# lab1.net
KiCad netlist of a schematic drawn in Altium Designer
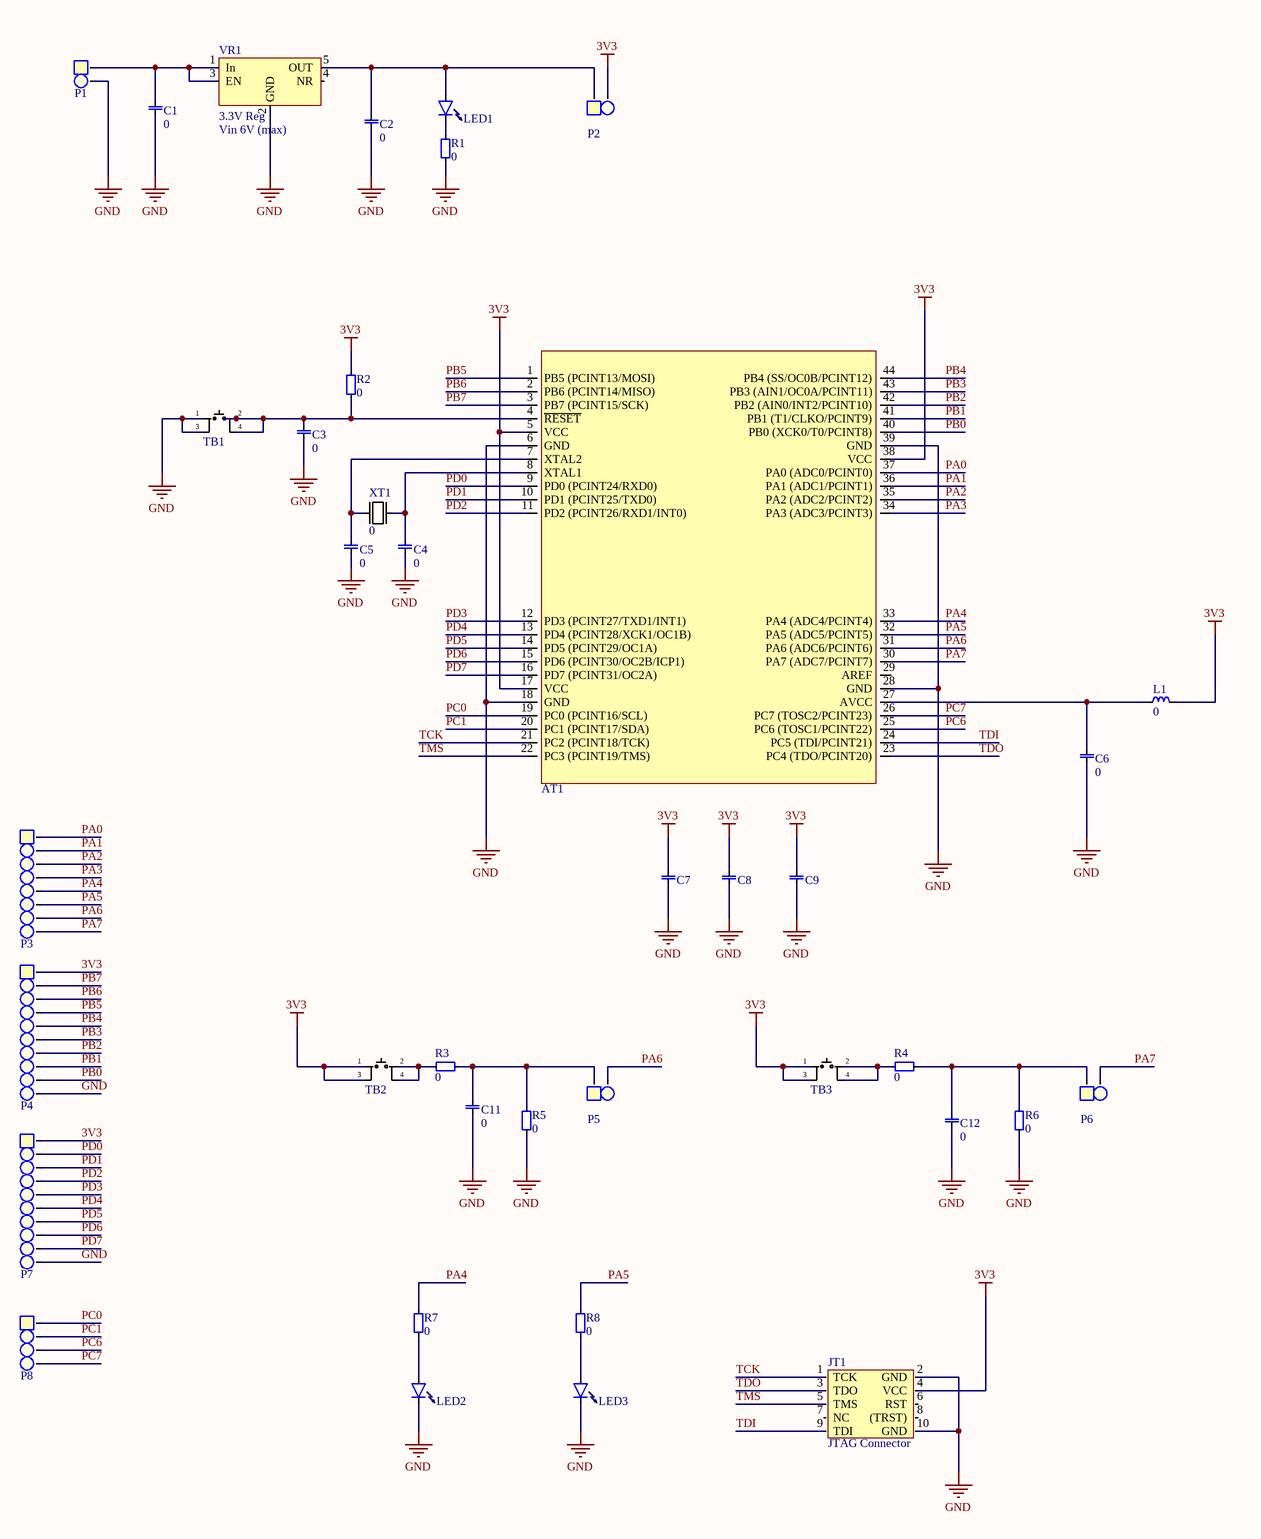
[diagram p0: lab1.SchDoc]

(export (version "E")
  (design (tool "Eeschema 10.0.6"))
  (components
    (comp (ref "AT1")
      (value "ATmega644PA")
      (footprint "TQFP-44")
      (description "ATmega644PA - Small but big and PicoPower")
      (libsource (lib "eitp15_lab1_lib") (part "ATmega644PA"))
    )
    (comp (ref "C1")
      (value "0")
      (footprint "1206, capasitor")
      (fields (field (name "Comment") "1206, capacitor"))
      (libsource (lib "eitp15_lab1_lib") (part "1206, capacitor"))
    )
    (comp (ref "C2")
      (value "0")
      (footprint "1206, capasitor")
      (fields (field (name "Comment") "1206, capacitor"))
      (libsource (lib "eitp15_lab1_lib") (part "1206, capacitor"))
    )
    (comp (ref "C3")
      (value "0")
      (footprint "1206, capasitor")
      (fields (field (name "Comment") "1206, capacitor"))
      (libsource (lib "eitp15_lab1_lib") (part "1206, capacitor"))
    )
    (comp (ref "C4")
      (value "0")
      (footprint "1206, capasitor")
      (fields (field (name "Comment") "1206, capacitor"))
      (libsource (lib "eitp15_lab1_lib") (part "1206, capacitor"))
    )
    (comp (ref "C5")
      (value "0")
      (footprint "1206, capasitor")
      (fields (field (name "Comment") "1206, capacitor"))
      (libsource (lib "eitp15_lab1_lib") (part "1206, capacitor"))
    )
    (comp (ref "C6")
      (value "0")
      (footprint "1206, capasitor")
      (fields (field (name "Comment") "1206, capacitor"))
      (libsource (lib "eitp15_lab1_lib") (part "1206, capacitor"))
    )
    (comp (ref "C7")
      (value "1206, capacitor")
      (footprint "1206, capasitor")
      (libsource (lib "eitp15_lab1_lib") (part "1206, capacitor"))
    )
    (comp (ref "C8")
      (value "1206, capacitor")
      (footprint "1206, capasitor")
      (libsource (lib "eitp15_lab1_lib") (part "1206, capacitor"))
    )
    (comp (ref "C9")
      (value "1206, capacitor")
      (footprint "1206, capasitor")
      (libsource (lib "eitp15_lab1_lib") (part "1206, capacitor"))
    )
    (comp (ref "C11")
      (value "0")
      (footprint "1206, capasitor")
      (fields (field (name "Comment") "1206, capacitor"))
      (libsource (lib "eitp15_lab1_lib") (part "1206, capacitor"))
    )
    (comp (ref "C12")
      (value "0")
      (footprint "1206, capasitor")
      (fields (field (name "Comment") "1206, capacitor"))
      (libsource (lib "eitp15_lab1_lib") (part "1206, capacitor"))
    )
    (comp (ref "JT1")
      (value "JTAG Connector")
      (footprint "Atmel_JTAG")
      (description "Atmel JTAG Connector")
      (libsource (lib "eitp15_lab1_lib") (part "Atmel JTAG"))
    )
    (comp (ref "L1")
      (value "0")
      (footprint "1812, coil")
      (fields (field (name "Comment") "Coil"))
      (libsource (lib "eitp15_lab1_lib") (part "Coil"))
    )
    (comp (ref "LED1")
      (value "0805, LED")
      (footprint "0805_led")
      (libsource (lib "eitp15_lab1_lib") (part "0805, LED"))
    )
    (comp (ref "LED2")
      (value "0805, LED")
      (footprint "0805_led")
      (libsource (lib "eitp15_lab1_lib") (part "0805, LED"))
    )
    (comp (ref "LED3")
      (value "0805, LED")
      (footprint "0805_led")
      (libsource (lib "eitp15_lab1_lib") (part "0805, LED"))
    )
    (comp (ref "P1")
      (value "1x2 Pin Header")
      (footprint "1x2HEADER")
      (description "2.54 mm, TH")
      (libsource (lib "eitp15_lab1_lib") (part "1x2 Pin Header"))
    )
    (comp (ref "P2")
      (value "1x2 Pin Header")
      (footprint "1x2HEADER")
      (description "2.54 mm, TH")
      (libsource (lib "") (part "1x2 Pin Header_1"))
    )
    (comp (ref "P3")
      (value "1x8 Pin Header")
      (footprint "1x8HEADER")
      (description "2.54 mm, TH")
      (libsource (lib "eitp15_lab1_lib") (part "1x8 Pin Header"))
    )
    (comp (ref "P4")
      (value "1x10 Pin Header")
      (footprint "1x10HEADER")
      (description "2.54 mm, TH")
      (libsource (lib "eitp15_lab1_lib") (part "1x10 Pin Header"))
    )
    (comp (ref "P5")
      (value "1x2 Pin Header")
      (footprint "1x2HEADER")
      (description "2.54 mm, TH")
      (libsource (lib "") (part "1x2 Pin Header_1"))
    )
    (comp (ref "P6")
      (value "1x2 Pin Header")
      (footprint "1x2HEADER")
      (description "2.54 mm, TH")
      (libsource (lib "") (part "1x2 Pin Header_1"))
    )
    (comp (ref "P7")
      (value "1x10 Pin Header")
      (footprint "1x10HEADER")
      (description "2.54 mm, TH")
      (libsource (lib "eitp15_lab1_lib") (part "1x10 Pin Header"))
    )
    (comp (ref "P8")
      (value "1x4 Pin Header")
      (footprint "1x4HEADER")
      (description "2.54 mm, TH")
      (libsource (lib "eitp15_lab1_lib") (part "1x4 Pin Header"))
    )
    (comp (ref "R1")
      (value "0")
      (footprint "1206")
      (description "Resistor")
      (fields (field (name "Comment") "1206, resistor"))
      (libsource (lib "eitp15_lab1_lib") (part "1206, resistor"))
    )
    (comp (ref "R2")
      (value "0")
      (footprint "1206")
      (description "Resistor")
      (fields (field (name "Comment") "1206, resistor"))
      (libsource (lib "eitp15_lab1_lib") (part "1206, resistor"))
    )
    (comp (ref "R3")
      (value "0")
      (footprint "1206")
      (description "Resistor")
      (fields (field (name "Comment") "1206, resistor"))
      (libsource (lib "eitp15_lab1_lib") (part "1206, resistor"))
    )
    (comp (ref "R4")
      (value "0")
      (footprint "1206")
      (description "Resistor")
      (fields (field (name "Comment") "1206, resistor"))
      (libsource (lib "eitp15_lab1_lib") (part "1206, resistor"))
    )
    (comp (ref "R5")
      (value "0")
      (footprint "1206")
      (description "Resistor")
      (fields (field (name "Comment") "1206, resistor"))
      (libsource (lib "eitp15_lab1_lib") (part "1206, resistor"))
    )
    (comp (ref "R6")
      (value "0")
      (footprint "1206")
      (description "Resistor")
      (fields (field (name "Comment") "1206, resistor"))
      (libsource (lib "eitp15_lab1_lib") (part "1206, resistor"))
    )
    (comp (ref "R7")
      (value "0")
      (footprint "1206")
      (description "Resistor")
      (fields (field (name "Comment") "1206, resistor"))
      (libsource (lib "eitp15_lab1_lib") (part "1206, resistor"))
    )
    (comp (ref "R8")
      (value "0")
      (footprint "1206")
      (description "Resistor")
      (fields (field (name "Comment") "1206, resistor"))
      (libsource (lib "eitp15_lab1_lib") (part "1206, resistor"))
    )
    (comp (ref "TB1")
      (value "Tactile Button")
      (footprint "Button smd")
      (description "Tactile Switch Small Low")
      (libsource (lib "eitp15_lab1_lib") (part "Button SMD"))
    )
    (comp (ref "TB2")
      (value "Tactile Button")
      (footprint "Button smd")
      (description "Tactile Switch Small Low")
      (libsource (lib "eitp15_lab1_lib") (part "Button SMD"))
    )
    (comp (ref "TB3")
      (value "Tactile Button")
      (footprint "Button smd")
      (description "Tactile Switch Small Low")
      (libsource (lib "eitp15_lab1_lib") (part "Button SMD"))
    )
    (comp (ref "VR1")
      (value "3.3V Reg")
      (footprint "SOT23-5")
      (description "3.3V Reg, Ultra-Low Noise, 200 mA")
      (fields (field (name "INPUT VOLTAGE") "Vin 6V (max)"))
      (libsource (lib "eitp15_lab1_lib") (part "TPS79333DBR"))
    )
    (comp (ref "XT1")
      (value "0")
      (footprint "XTAL_SMD_LP")
      (description "16 MHz, SMD, 5mm x 3,2mm, 30 ppm")
      (fields (field (name "Comment") "XTAL TXC 7A"))
      (libsource (lib "eitp15_lab1_lib") (part "XTAL TXC 7A"))
    )
  )
  (nets
    (net (code "1") (name "/PA0") (class "Default")
      (node (ref "AT1") (pin "37") (pinfunction "PA0_(ADC0/PCINT0)_37") (pintype "passive"))
      (node (ref "P3") (pin "1") (pinfunction "1_1") (pintype "passive"))
    )
    (net (code "2") (name "/PA1") (class "Default")
      (node (ref "AT1") (pin "36") (pinfunction "PA1_(ADC1/PCINT1)_36") (pintype "passive"))
      (node (ref "P3") (pin "2") (pinfunction "2_2") (pintype "passive"))
    )
    (net (code "3") (name "/PA2") (class "Default")
      (node (ref "AT1") (pin "35") (pinfunction "PA2_(ADC2/PCINT2)_35") (pintype "passive"))
      (node (ref "P3") (pin "3") (pinfunction "3_3") (pintype "passive"))
    )
    (net (code "4") (name "/PA3") (class "Default")
      (node (ref "AT1") (pin "34") (pinfunction "PA3_(ADC3/PCINT3)_34") (pintype "passive"))
      (node (ref "P3") (pin "4") (pinfunction "4_4") (pintype "passive"))
    )
    (net (code "5") (name "/PA4") (class "Default")
      (node (ref "AT1") (pin "33") (pinfunction "PA4_(ADC4/PCINT4)_33") (pintype "passive"))
      (node (ref "P3") (pin "5") (pinfunction "5_5") (pintype "passive"))
      (node (ref "R7") (pin "0") (pinfunction "0_0") (pintype "passive"))
    )
    (net (code "6") (name "/PA5") (class "Default")
      (node (ref "AT1") (pin "32") (pinfunction "PA5_(ADC5/PCINT5)_32") (pintype "passive"))
      (node (ref "P3") (pin "6") (pinfunction "6_6") (pintype "passive"))
      (node (ref "R8") (pin "0") (pinfunction "0_0") (pintype "passive"))
    )
    (net (code "7") (name "/PA6") (class "Default")
      (node (ref "AT1") (pin "31") (pinfunction "PA6_(ADC6/PCINT6)_31") (pintype "passive"))
      (node (ref "P3") (pin "7") (pinfunction "7_7") (pintype "passive"))
      (node (ref "P5") (pin "2") (pinfunction "2_2") (pintype "passive"))
    )
    (net (code "8") (name "/PA7") (class "Default")
      (node (ref "AT1") (pin "30") (pinfunction "PA7_(ADC7/PCINT7)_30") (pintype "passive"))
      (node (ref "P3") (pin "8") (pinfunction "8_8") (pintype "passive"))
      (node (ref "P6") (pin "2") (pinfunction "2_2") (pintype "passive"))
    )
    (net (code "9") (name "/PB0") (class "Default")
      (node (ref "AT1") (pin "40") (pinfunction "PB0_(XCK0/T0/PCINT8)_40") (pintype "passive"))
      (node (ref "P4") (pin "9") (pinfunction "9_9") (pintype "passive"))
    )
    (net (code "10") (name "/PB1") (class "Default")
      (node (ref "AT1") (pin "41") (pinfunction "PB1_(T1/CLKO/PCINT9)_41") (pintype "passive"))
      (node (ref "P4") (pin "8") (pinfunction "8_8") (pintype "passive"))
    )
    (net (code "11") (name "/PB2") (class "Default")
      (node (ref "AT1") (pin "42") (pinfunction "PB2_(AIN0/INT2/PCINT10)_42") (pintype "passive"))
      (node (ref "P4") (pin "7") (pinfunction "7_7") (pintype "passive"))
    )
    (net (code "12") (name "/PB3") (class "Default")
      (node (ref "AT1") (pin "43") (pinfunction "PB3_(AIN1/OC0A/PCINT11)_43") (pintype "passive"))
      (node (ref "P4") (pin "6") (pinfunction "6_6") (pintype "passive"))
    )
    (net (code "13") (name "/PB4") (class "Default")
      (node (ref "AT1") (pin "44") (pinfunction "PB4_(SS/OC0B/PCINT12)_44") (pintype "passive"))
      (node (ref "P4") (pin "5") (pinfunction "5_5") (pintype "passive"))
    )
    (net (code "14") (name "/PB5") (class "Default")
      (node (ref "AT1") (pin "1") (pinfunction "PB5_(PCINT13/MOSI)_1") (pintype "passive"))
      (node (ref "P4") (pin "4") (pinfunction "4_4") (pintype "passive"))
    )
    (net (code "15") (name "/PB6") (class "Default")
      (node (ref "AT1") (pin "2") (pinfunction "PB6_(PCINT14/MISO)_2") (pintype "passive"))
      (node (ref "P4") (pin "3") (pinfunction "3_3") (pintype "passive"))
    )
    (net (code "16") (name "/PB7") (class "Default")
      (node (ref "AT1") (pin "3") (pinfunction "PB7_(PCINT15/SCK)_3") (pintype "passive"))
      (node (ref "P4") (pin "2") (pinfunction "2_2") (pintype "passive"))
    )
    (net (code "17") (name "/PC0") (class "Default")
      (node (ref "AT1") (pin "19") (pinfunction "PC0_(PCINT16/SCL)_19") (pintype "passive"))
      (node (ref "P8") (pin "1") (pinfunction "1_1") (pintype "passive"))
    )
    (net (code "18") (name "/PC1") (class "Default")
      (node (ref "AT1") (pin "20") (pinfunction "PC1_(PCINT17/SDA)_20") (pintype "passive"))
      (node (ref "P8") (pin "2") (pinfunction "2_2") (pintype "passive"))
    )
    (net (code "19") (name "/PC6") (class "Default")
      (node (ref "AT1") (pin "25") (pinfunction "PC6_(TOSC1/PCINT22)_25") (pintype "passive"))
      (node (ref "P8") (pin "3") (pinfunction "3_3") (pintype "passive"))
    )
    (net (code "20") (name "/PC7") (class "Default")
      (node (ref "AT1") (pin "26") (pinfunction "PC7_(TOSC2/PCINT23)_26") (pintype "passive"))
      (node (ref "P8") (pin "4") (pinfunction "4_4") (pintype "passive"))
    )
    (net (code "21") (name "/PD0") (class "Default")
      (node (ref "AT1") (pin "9") (pinfunction "PD0_(PCINT24/RXD0)_9") (pintype "passive"))
      (node (ref "P7") (pin "2") (pinfunction "2_2") (pintype "passive"))
    )
    (net (code "22") (name "/PD1") (class "Default")
      (node (ref "AT1") (pin "10") (pinfunction "PD1_(PCINT25/TXD0)_10") (pintype "passive"))
      (node (ref "P7") (pin "3") (pinfunction "3_3") (pintype "passive"))
    )
    (net (code "23") (name "/PD2") (class "Default")
      (node (ref "AT1") (pin "11") (pinfunction "PD2_(PCINT26/RXD1/INT0)_11") (pintype "passive"))
      (node (ref "P7") (pin "4") (pinfunction "4_4") (pintype "passive"))
    )
    (net (code "24") (name "/PD3") (class "Default")
      (node (ref "AT1") (pin "12") (pinfunction "PD3_(PCINT27/TXD1/INT1)_12") (pintype "passive"))
      (node (ref "P7") (pin "5") (pinfunction "5_5") (pintype "passive"))
    )
    (net (code "25") (name "/PD4") (class "Default")
      (node (ref "AT1") (pin "13") (pinfunction "PD4_(PCINT28/XCK1/OC1B)_13") (pintype "passive"))
      (node (ref "P7") (pin "6") (pinfunction "6_6") (pintype "passive"))
    )
    (net (code "26") (name "/PD5") (class "Default")
      (node (ref "AT1") (pin "14") (pinfunction "PD5_(PCINT29/OC1A)_14") (pintype "passive"))
      (node (ref "P7") (pin "7") (pinfunction "7_7") (pintype "passive"))
    )
    (net (code "27") (name "/PD6") (class "Default")
      (node (ref "AT1") (pin "15") (pinfunction "PD6_(PCINT30/OC2B/ICP1)_15") (pintype "passive"))
      (node (ref "P7") (pin "8") (pinfunction "8_8") (pintype "passive"))
    )
    (net (code "28") (name "/PD7") (class "Default")
      (node (ref "AT1") (pin "16") (pinfunction "PD7_(PCINT31/OC2A)_16") (pintype "passive"))
      (node (ref "P7") (pin "9") (pinfunction "9_9") (pintype "passive"))
    )
    (net (code "29") (name "/TCK") (class "Default")
      (node (ref "AT1") (pin "21") (pinfunction "PC2_(PCINT18/TCK)_21") (pintype "passive"))
      (node (ref "JT1") (pin "1") (pinfunction "TCK_1") (pintype "passive"))
    )
    (net (code "30") (name "/TDI") (class "Default")
      (node (ref "AT1") (pin "24") (pinfunction "PC5_(TDI/PCINT21)_24") (pintype "passive"))
      (node (ref "JT1") (pin "9") (pinfunction "TDI_9") (pintype "passive"))
    )
    (net (code "31") (name "/TDO") (class "Default")
      (node (ref "AT1") (pin "23") (pinfunction "PC4_(TDO/PCINT20)_23") (pintype "passive"))
      (node (ref "JT1") (pin "3") (pinfunction "TDO_3") (pintype "passive"))
    )
    (net (code "32") (name "/TMS") (class "Default")
      (node (ref "AT1") (pin "22") (pinfunction "PC3_(PCINT19/TMS)_22") (pintype "passive"))
      (node (ref "JT1") (pin "5") (pinfunction "TMS_5") (pintype "passive"))
    )
    (net (code "33") (name "3V3") (class "Default")
      (node (ref "AT1") (pin "17") (pinfunction "VCC_17") (pintype "passive"))
      (node (ref "AT1") (pin "38") (pinfunction "VCC_38") (pintype "passive"))
      (node (ref "AT1") (pin "5") (pinfunction "VCC_5") (pintype "passive"))
      (node (ref "C7") (pin "1") (pinfunction "1_1") (pintype "passive"))
      (node (ref "C8") (pin "1") (pinfunction "1_1") (pintype "passive"))
      (node (ref "C9") (pin "1") (pinfunction "1_1") (pintype "passive"))
      (node (ref "JT1") (pin "4") (pinfunction "VCC_4") (pintype "passive"))
      (node (ref "L1") (pin "1") (pinfunction "1_1") (pintype "passive"))
      (node (ref "P2") (pin "2") (pinfunction "2_2") (pintype "passive"))
      (node (ref "P4") (pin "1") (pinfunction "1_1") (pintype "passive"))
      (node (ref "P7") (pin "1") (pinfunction "1_1") (pintype "passive"))
      (node (ref "R2") (pin "0") (pinfunction "0_0") (pintype "passive"))
      (node (ref "TB2") (pin "1") (pinfunction "1_1") (pintype "passive"))
      (node (ref "TB2") (pin "3") (pinfunction "3_3") (pintype "passive"))
      (node (ref "TB3") (pin "1") (pinfunction "1_1") (pintype "passive"))
      (node (ref "TB3") (pin "3") (pinfunction "3_3") (pintype "passive"))
    )
    (net (code "34") (name "GND") (class "Default")
      (node (ref "AT1") (pin "18") (pinfunction "GND_18") (pintype "passive"))
      (node (ref "AT1") (pin "28") (pinfunction "GND_28") (pintype "passive"))
      (node (ref "AT1") (pin "39") (pinfunction "GND_39") (pintype "passive"))
      (node (ref "AT1") (pin "6") (pinfunction "GND_6") (pintype "passive"))
      (node (ref "C1") (pin "0") (pinfunction "0_0") (pintype "passive"))
      (node (ref "C11") (pin "0") (pinfunction "0_0") (pintype "passive"))
      (node (ref "C12") (pin "0") (pinfunction "0_0") (pintype "passive"))
      (node (ref "C2") (pin "0") (pinfunction "0_0") (pintype "passive"))
      (node (ref "C3") (pin "0") (pinfunction "0_0") (pintype "passive"))
      (node (ref "C4") (pin "0") (pinfunction "0_0") (pintype "passive"))
      (node (ref "C5") (pin "0") (pinfunction "0_0") (pintype "passive"))
      (node (ref "C6") (pin "0") (pinfunction "0_0") (pintype "passive"))
      (node (ref "C7") (pin "0") (pinfunction "0_0") (pintype "passive"))
      (node (ref "C8") (pin "0") (pinfunction "0_0") (pintype "passive"))
      (node (ref "C9") (pin "0") (pinfunction "0_0") (pintype "passive"))
      (node (ref "JT1") (pin "10") (pinfunction "GND_10") (pintype "passive"))
      (node (ref "JT1") (pin "2") (pinfunction "GND_2") (pintype "passive"))
      (node (ref "LED2") (pin "0") (pinfunction "Cathode_0") (pintype "passive"))
      (node (ref "LED3") (pin "0") (pinfunction "Cathode_0") (pintype "passive"))
      (node (ref "P1") (pin "2") (pinfunction "2_2") (pintype "passive"))
      (node (ref "P4") (pin "10") (pinfunction "10_10") (pintype "passive"))
      (node (ref "P7") (pin "10") (pinfunction "10_10") (pintype "passive"))
      (node (ref "R1") (pin "1") (pinfunction "1_1") (pintype "passive"))
      (node (ref "R5") (pin "1") (pinfunction "1_1") (pintype "passive"))
      (node (ref "R6") (pin "1") (pinfunction "1_1") (pintype "passive"))
      (node (ref "TB1") (pin "1") (pinfunction "1_1") (pintype "passive"))
      (node (ref "TB1") (pin "3") (pinfunction "3_3") (pintype "passive"))
      (node (ref "VR1") (pin "2") (pinfunction "GND_2") (pintype "passive"))
    )
    (net (code "35") (name "Net-(AT1-AVCC)") (class "Default")
      (node (ref "AT1") (pin "27") (pinfunction "AVCC_27") (pintype "passive"))
      (node (ref "C6") (pin "1") (pinfunction "1_1") (pintype "passive"))
      (node (ref "L1") (pin "2") (pinfunction "2_2") (pintype "passive"))
    )
    (net (code "36") (name "Net-(AT1-XTAL1)") (class "Default")
      (node (ref "AT1") (pin "8") (pinfunction "XTAL1_8") (pintype "passive"))
      (node (ref "C4") (pin "1") (pinfunction "1_1") (pintype "passive"))
      (node (ref "XT1") (pin "2") (pinfunction "2_2") (pintype "passive"))
    )
    (net (code "37") (name "Net-(AT1-XTAL2)") (class "Default")
      (node (ref "AT1") (pin "7") (pinfunction "XTAL2_7") (pintype "passive"))
      (node (ref "C5") (pin "1") (pinfunction "1_1") (pintype "passive"))
      (node (ref "XT1") (pin "1") (pinfunction "1_1") (pintype "passive"))
    )
    (net (code "38") (name "Net-(AT1-~{RESET})") (class "Default")
      (node (ref "AT1") (pin "4") (pinfunction "~{RESET}_4") (pintype "passive"))
      (node (ref "C3") (pin "1") (pinfunction "1_1") (pintype "passive"))
      (node (ref "R2") (pin "1") (pinfunction "1_1") (pintype "passive"))
      (node (ref "TB1") (pin "2") (pinfunction "2_2") (pintype "passive"))
      (node (ref "TB1") (pin "4") (pinfunction "4_4") (pintype "passive"))
    )
    (net (code "39") (name "Net-(C11-Pad1)") (class "Default")
      (node (ref "C11") (pin "1") (pinfunction "1_1") (pintype "passive"))
      (node (ref "P5") (pin "1") (pinfunction "1_1") (pintype "passive"))
      (node (ref "R3") (pin "0") (pinfunction "0_0") (pintype "passive"))
      (node (ref "R5") (pin "0") (pinfunction "0_0") (pintype "passive"))
    )
    (net (code "40") (name "Net-(C12-Pad1)") (class "Default")
      (node (ref "C12") (pin "1") (pinfunction "1_1") (pintype "passive"))
      (node (ref "P6") (pin "1") (pinfunction "1_1") (pintype "passive"))
      (node (ref "R4") (pin "0") (pinfunction "0_0") (pintype "passive"))
      (node (ref "R6") (pin "0") (pinfunction "0_0") (pintype "passive"))
    )
    (net (code "41") (name "Net-(LED1-Cathode)") (class "Default")
      (node (ref "LED1") (pin "0") (pinfunction "Cathode_0") (pintype "passive"))
      (node (ref "R1") (pin "0") (pinfunction "0_0") (pintype "passive"))
    )
    (net (code "42") (name "Net-(LED2-Pad1)") (class "Default")
      (node (ref "LED2") (pin "1") (pinfunction "1_1") (pintype "passive"))
      (node (ref "R7") (pin "1") (pinfunction "1_1") (pintype "passive"))
    )
    (net (code "43") (name "Net-(LED3-Pad1)") (class "Default")
      (node (ref "LED3") (pin "1") (pinfunction "1_1") (pintype "passive"))
      (node (ref "R8") (pin "1") (pinfunction "1_1") (pintype "passive"))
    )
    (net (code "44") (name "Net-(R3-Pad1)") (class "Default")
      (node (ref "R3") (pin "1") (pinfunction "1_1") (pintype "passive"))
      (node (ref "TB2") (pin "2") (pinfunction "2_2") (pintype "passive"))
      (node (ref "TB2") (pin "4") (pinfunction "4_4") (pintype "passive"))
    )
    (net (code "45") (name "Net-(R4-Pad1)") (class "Default")
      (node (ref "R4") (pin "1") (pinfunction "1_1") (pintype "passive"))
      (node (ref "TB3") (pin "2") (pinfunction "2_2") (pintype "passive"))
      (node (ref "TB3") (pin "4") (pinfunction "4_4") (pintype "passive"))
    )
    (net (code "46") (name "Net-(VR1-EN)") (class "Default")
      (node (ref "C1") (pin "1") (pinfunction "1_1") (pintype "passive"))
      (node (ref "P1") (pin "1") (pinfunction "1_1") (pintype "passive"))
      (node (ref "VR1") (pin "1") (pinfunction "In_1") (pintype "passive"))
      (node (ref "VR1") (pin "3") (pinfunction "EN_3") (pintype "passive"))
    )
    (net (code "47") (name "Net-(VR1-OUT)") (class "Default")
      (node (ref "C2") (pin "1") (pinfunction "1_1") (pintype "passive"))
      (node (ref "LED1") (pin "1") (pinfunction "1_1") (pintype "passive"))
      (node (ref "P2") (pin "1") (pinfunction "1_1") (pintype "passive"))
      (node (ref "VR1") (pin "5") (pinfunction "OUT_5") (pintype "passive"))
    )
    (net (code "48") (name "unconnected-(AT1-AREF-Pad29)") (class "Default")
      (node (ref "AT1") (pin "29") (pinfunction "AREF_29") (pintype "passive"))
    )
    (net (code "49") (name "unconnected-(JT1-(TRST)-Pad8)") (class "Default")
      (node (ref "JT1") (pin "8") (pinfunction "(TRST)_8") (pintype "passive"))
    )
    (net (code "50") (name "unconnected-(JT1-NC-Pad7)") (class "Default")
      (node (ref "JT1") (pin "7") (pinfunction "NC_7") (pintype "passive"))
    )
    (net (code "51") (name "unconnected-(JT1-RST-Pad6)") (class "Default")
      (node (ref "JT1") (pin "6") (pinfunction "RST_6") (pintype "passive"))
    )
    (net (code "52") (name "unconnected-(VR1-NR-Pad4)") (class "Default")
      (node (ref "VR1") (pin "4") (pinfunction "NR_4") (pintype "passive"))
    )
  )
)
